# DVT-ClockGenerator.net
KiCad netlist of a schematic drawn in Altium Designer
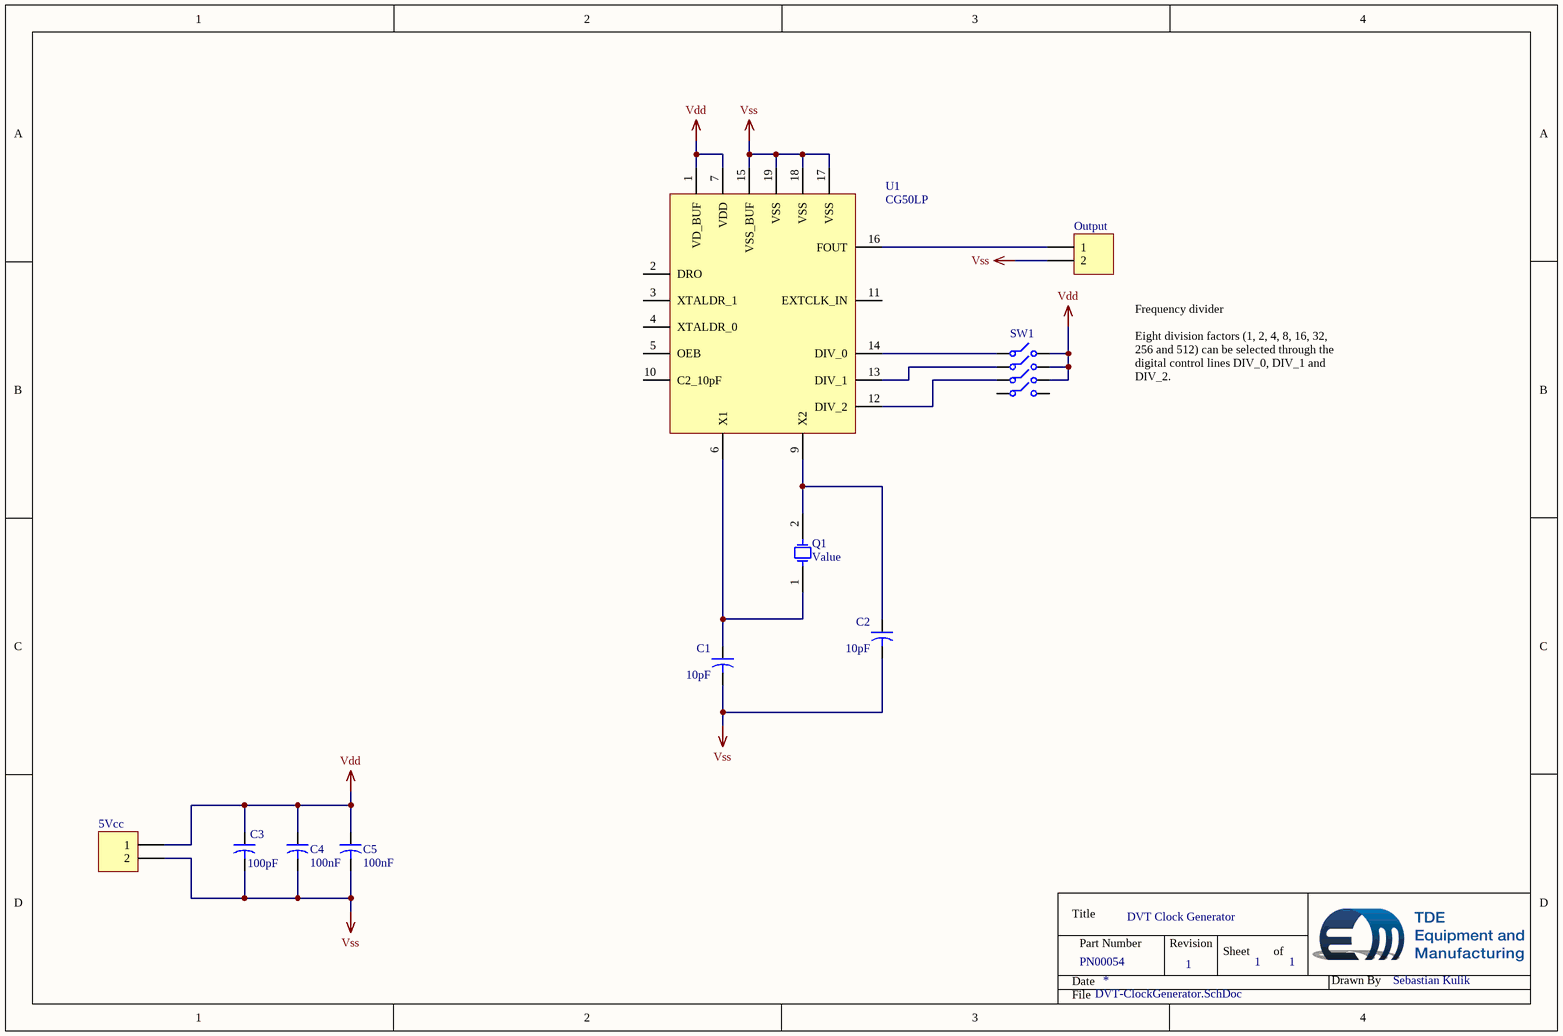
[diagram p0: DVT-ClockGenerator.SchDoc]

(export (version "E")
  (design (tool "Eeschema 10.0.6"))
  (components
    (comp (ref "5Vcc")
      (value "PHOENIX_1715721")
      (footprint "Phoenix-2-5_08")
      (description "Phoenix, 2 pol, 5.08mm, 22A, 715721")
      (fields (field (name "MANUFACTURER") "Phoenix") (field (name "PUBLISHER") "Sebastian Kulik"))
      (libsource (lib "") (part "2Pol_1715721_1"))
    )
    (comp (ref "C1")
      (value "10pF")
      (footprint "Dummy-10mm")
      (description "Capacitor-Dummy-THT")
      (fields (field (name "MANUFACTURER") "Kemet") (field (name "PUBLISHER") "Sebastian Kulik"))
      (libsource (lib "Capacitors") (part "Capacitor-Dummy-THT"))
    )
    (comp (ref "C2")
      (value "10pF")
      (footprint "Dummy-10mm")
      (description "Capacitor-Dummy-THT")
      (fields (field (name "MANUFACTURER") "Kemet") (field (name "PUBLISHER") "Sebastian Kulik"))
      (libsource (lib "Capacitors") (part "Capacitor-Dummy-THT"))
    )
    (comp (ref "C3")
      (value "100pF")
      (footprint "Dummy-10mm")
      (description "Capacitor-Dummy-THT")
      (fields (field (name "PUBLISHER") "Sebastian Kulik"))
      (libsource (lib "Capacitors") (part "Capacitor-Dummy-THT"))
    )
    (comp (ref "C4")
      (value "100nF")
      (footprint "Dummy-10mm")
      (description "Capacitor-Dummy-THT")
      (fields (field (name "PUBLISHER") "Sebastian Kulik"))
      (libsource (lib "Capacitors") (part "Capacitor-Dummy-THT"))
    )
    (comp (ref "C5")
      (value "100nF")
      (footprint "Dummy-10mm")
      (description "Capacitor-Dummy-THT")
      (fields (field (name "PUBLISHER") "Sebastian Kulik"))
      (libsource (lib "Capacitors") (part "Capacitor-Dummy-THT"))
    )
    (comp (ref "Output")
      (value "PHOENIX_1715721")
      (footprint "Phoenix-2-5_08")
      (description "Phoenix, 2 pol, 5.08mm, 22A, 715721")
      (fields (field (name "MANUFACTURER") "Phoenix") (field (name "PUBLISHER") "Sebastian Kulik"))
      (libsource (lib "Connectors") (part "2Pol_1715721"))
    )
    (comp (ref "Q1")
      (value "Value")
      (footprint "HC49-U")
      (description "Crystal_HC49-U Uni")
      (fields (field (name "Comment") "Crystal_HC49-U_THT") (field (name "PUBLISHER") "Sebastian Kulik"))
      (libsource (lib "Passives") (part "Crystal_HC49-U"))
    )
    (comp (ref "SW1")
      (value "WS-DITV-4DIP")
      (footprint "DIP-8-Ceramic-HT")
      (description "4 way DIP switch")
      (fields (field (name "MANUFACTURER") "WE") (field (name "PUBLISHER") "Sebastian Kulik"))
      (libsource (lib "Mechanical") (part "WS-DITV-4DIP"))
    )
    (comp (ref "U1")
      (value "CG50LP")
      (footprint "TDFP16")
      (description "VERSATILE CRYSTAL CLOCK GENERATOR - 2ND GEN")
      (fields (field (name "MANUFACTURER") "CISSOID") (field (name "PUBLISHER") "Sebastian Kulik"))
      (libsource (lib "ICs") (part "CG50LP"))
    )
  )
  (nets
    (net (code "1") (name "Net-(Q1-E{slash}D)") (class "Default")
      (node (ref "C1") (pin "1") (pinfunction "1_1") (pintype "passive"))
      (node (ref "Q1") (pin "1") (pinfunction "E/D_1") (pintype "passive"))
      (node (ref "U1") (pin "6") (pinfunction "X1_6") (pintype "power_in"))
    )
    (net (code "2") (name "Net-(Q1-GND)") (class "Default")
      (node (ref "C2") (pin "1") (pinfunction "1_1") (pintype "passive"))
      (node (ref "Q1") (pin "2") (pinfunction "GND_2") (pintype "passive"))
      (node (ref "U1") (pin "9") (pinfunction "X2_9") (pintype "power_in"))
    )
    (net (code "3") (name "Net-(U1-DIV_0)") (class "Default")
      (node (ref "SW1") (pin "1") (pinfunction "1_1") (pintype "passive"))
      (node (ref "U1") (pin "14") (pinfunction "DIV_0_14") (pintype "power_in"))
    )
    (net (code "4") (name "Net-(U1-DIV_1)") (class "Default")
      (node (ref "SW1") (pin "2") (pinfunction "2_2") (pintype "passive"))
      (node (ref "U1") (pin "13") (pinfunction "DIV_1_13") (pintype "power_in"))
    )
    (net (code "5") (name "Net-(U1-DIV_2)") (class "Default")
      (node (ref "SW1") (pin "3") (pinfunction "3_3") (pintype "passive"))
      (node (ref "U1") (pin "12") (pinfunction "DIV_2_12") (pintype "power_in"))
    )
    (net (code "6") (name "Net-(U1-FOUT)") (class "Default")
      (node (ref "Output") (pin "1") (pinfunction "1_1") (pintype "passive"))
      (node (ref "U1") (pin "16") (pinfunction "FOUT_16") (pintype "power_in"))
    )
    (net (code "7") (name "Vdd") (class "Default")
      (node (ref "5Vcc") (pin "1") (pinfunction "1_1") (pintype "passive"))
      (node (ref "C3") (pin "1") (pinfunction "1_1") (pintype "passive"))
      (node (ref "C4") (pin "1") (pinfunction "1_1") (pintype "passive"))
      (node (ref "C5") (pin "1") (pinfunction "1_1") (pintype "passive"))
      (node (ref "SW1") (pin "6") (pinfunction "6_6") (pintype "passive"))
      (node (ref "SW1") (pin "7") (pinfunction "7_7") (pintype "passive"))
      (node (ref "SW1") (pin "8") (pinfunction "8_8") (pintype "passive"))
      (node (ref "U1") (pin "1") (pinfunction "VD_BUF_1") (pintype "passive"))
      (node (ref "U1") (pin "7") (pinfunction "VDD_7") (pintype "power_in"))
    )
    (net (code "8") (name "Vss") (class "Default")
      (node (ref "5Vcc") (pin "2") (pinfunction "2_2") (pintype "passive"))
      (node (ref "C1") (pin "2") (pinfunction "2_2") (pintype "passive"))
      (node (ref "C2") (pin "2") (pinfunction "2_2") (pintype "passive"))
      (node (ref "C3") (pin "2") (pinfunction "2_2") (pintype "passive"))
      (node (ref "C4") (pin "2") (pinfunction "2_2") (pintype "passive"))
      (node (ref "C5") (pin "2") (pinfunction "2_2") (pintype "passive"))
      (node (ref "Output") (pin "2") (pinfunction "2_2") (pintype "passive"))
      (node (ref "U1") (pin "15") (pinfunction "VSS_BUF_15") (pintype "passive"))
      (node (ref "U1") (pin "17") (pinfunction "VSS_17") (pintype "power_in"))
      (node (ref "U1") (pin "18") (pinfunction "VSS_18") (pintype "power_in"))
      (node (ref "U1") (pin "19") (pinfunction "VSS_19") (pintype "power_in"))
    )
    (net (code "9") (name "unconnected-(SW1-Pad4)") (class "Default")
      (node (ref "SW1") (pin "4") (pinfunction "4_4") (pintype "passive"))
    )
    (net (code "10") (name "unconnected-(SW1-Pad5)") (class "Default")
      (node (ref "SW1") (pin "5") (pinfunction "5_5") (pintype "passive"))
    )
    (net (code "11") (name "unconnected-(U1-C2_10pF-Pad10)") (class "Default")
      (node (ref "U1") (pin "10") (pinfunction "C2_10pF_10") (pintype "power_in"))
    )
    (net (code "12") (name "unconnected-(U1-DRO-Pad2)") (class "Default")
      (node (ref "U1") (pin "2") (pinfunction "DRO_2") (pintype "passive"))
    )
    (net (code "13") (name "unconnected-(U1-EXTCLK_IN-Pad11)") (class "Default")
      (node (ref "U1") (pin "11") (pinfunction "EXTCLK_IN_11") (pintype "passive"))
    )
    (net (code "14") (name "unconnected-(U1-OEB-Pad5)") (class "Default")
      (node (ref "U1") (pin "5") (pinfunction "OEB_5") (pintype "passive"))
    )
    (net (code "15") (name "unconnected-(U1-XTALDR_0-Pad4)") (class "Default")
      (node (ref "U1") (pin "4") (pinfunction "XTALDR_0_4") (pintype "power_in"))
    )
    (net (code "16") (name "unconnected-(U1-XTALDR_1-Pad3)") (class "Default")
      (node (ref "U1") (pin "3") (pinfunction "XTALDR_1_3") (pintype "passive"))
    )
  )
)
